# LINK2_LPC4322_PERIPH-DEBUG.net
KiCad netlist of a schematic drawn in Altium Designer
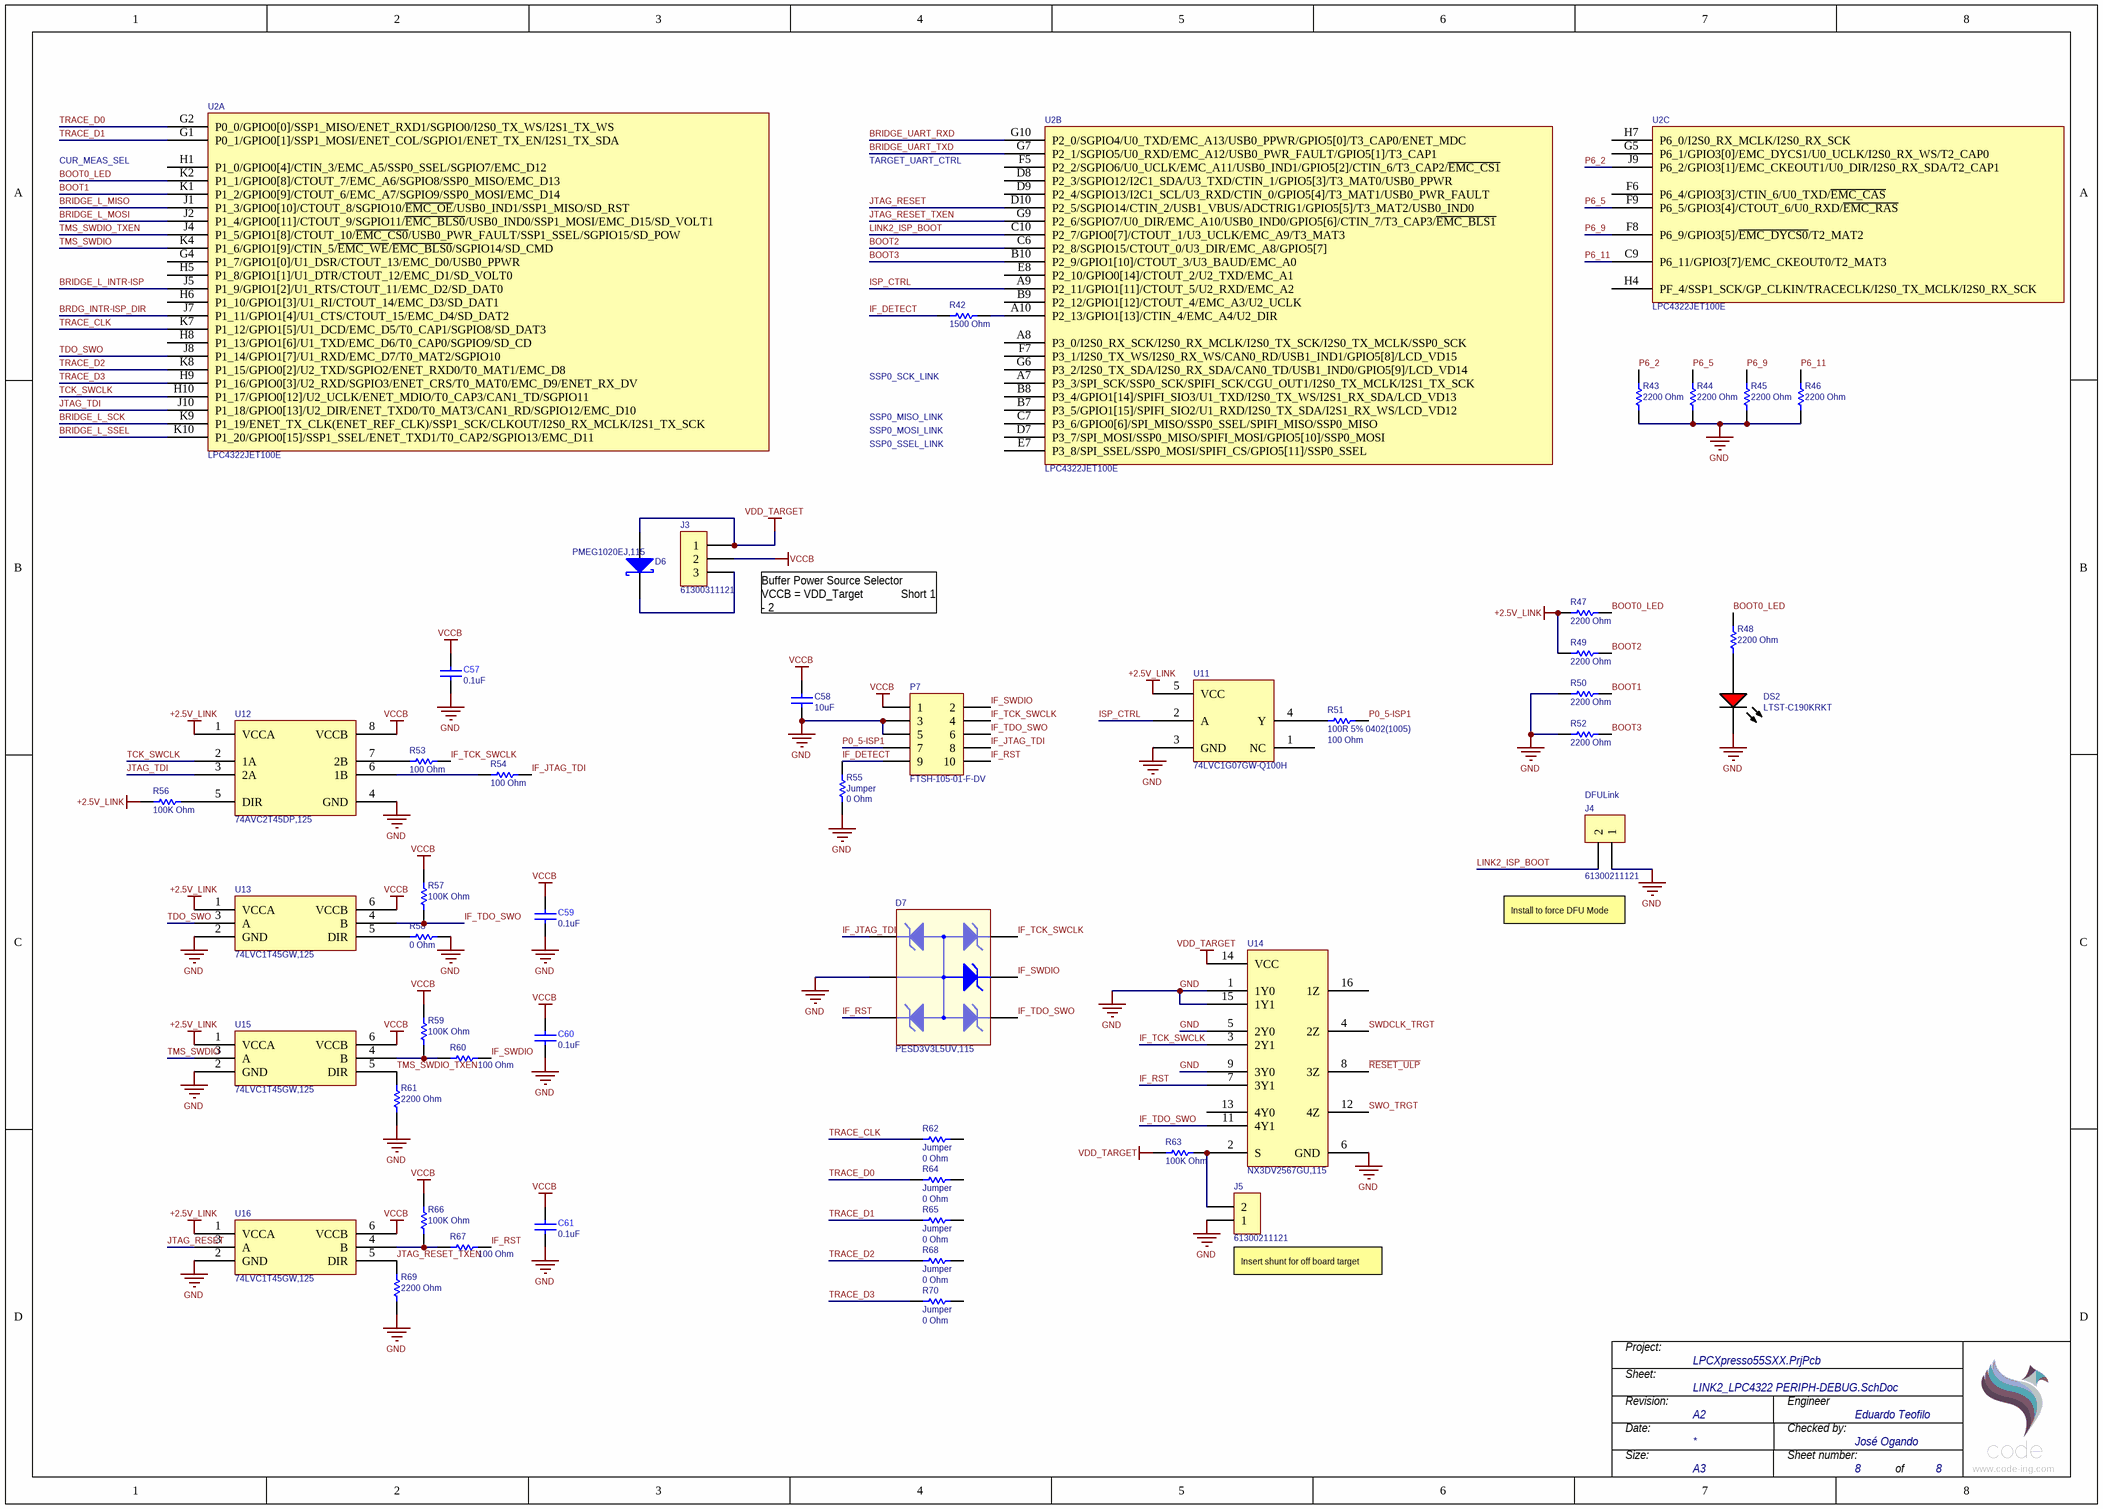
[diagram p0: LINK2_LPC4322 PERIPH-DEBUG.SchDoc]

(export (version "E")
  (design (tool "Eeschema 10.0.6"))
  (components
    (comp (ref "C57")
      (value "0.1uF")
      (footprint "CAPC1005")
      (description "Capacitor, Yageo, Ceramic, 0.1uF 10% 16V 0402 (1005) X7R")
      (fields
        (field (name "TOLERANCE") "10 %")
        (field (name "Comment") "CC0402KRX7R7BB104")
        (field (name "PUBLISHER") "Altium")
      )
      (libsource (lib "Altium Content Vault") (part "CMP-0001-00074-1"))
    )
    (comp (ref "C58")
      (value "10uF")
      (footprint "CAPC0805(2012)145_L")
      (description "CAP 10uF 10V ±10% 0805 (2012 Metric) Thickness 1.45mm SMD")
      (fields (field (name "TOLERANCE") "Â±10%") (field (name "Comment") "CAP 10uF 10V 0805(2012)"))
      (libsource (lib "Altium Content Vault") (part "CMP-1036-04922-1"))
    )
    (comp (ref "C59")
      (value "0.1uF")
      (footprint "CAPC1005")
      (description "Capacitor, Yageo, Ceramic, 0.1uF 10% 16V 0402 (1005) X7R")
      (fields
        (field (name "TOLERANCE") "10 %")
        (field (name "Comment") "CC0402KRX7R7BB104")
        (field (name "PUBLISHER") "Altium")
      )
      (libsource (lib "Altium Content Vault") (part "CMP-0001-00074-1"))
    )
    (comp (ref "C60")
      (value "0.1uF")
      (footprint "CAPC1005")
      (description "Capacitor, Yageo, Ceramic, 0.1uF 10% 16V 0402 (1005) X7R")
      (fields
        (field (name "TOLERANCE") "10 %")
        (field (name "Comment") "CC0402KRX7R7BB104")
        (field (name "PUBLISHER") "Altium")
      )
      (libsource (lib "Altium Content Vault") (part "CMP-0001-00074-1"))
    )
    (comp (ref "C61")
      (value "0.1uF")
      (footprint "CAPC1005")
      (description "Capacitor, Yageo, Ceramic, 0.1uF 10% 16V 0402 (1005) X7R")
      (fields
        (field (name "TOLERANCE") "10 %")
        (field (name "Comment") "CC0402KRX7R7BB104")
        (field (name "PUBLISHER") "Altium")
      )
      (libsource (lib "Altium Content Vault") (part "CMP-0001-00074-1"))
    )
    (comp (ref "D6")
      (value "PMEG1020EJ,115")
      (footprint "SOD-323F, SC90")
      (description "DIODE SCHOTTKY 10V 2A SOD323F")
      (fields
        (field (name "MANUFACTURER") "Nexperia USA Inc.")
        (field (name "CREATED BY") "eteofilo")
        (field (name "MODIFIED BY") "*")
      )
      (libsource (lib "Diodes, Rectifiers - Single") (part "PMEG1020EJ,115"))
    )
    (comp (ref "D7")
      (value "PESD3V3L5UV,115")
      (footprint "SOT-666")
      (description "TVS DIODE 3.3V 12V SOT666")
      (fields
        (field (name "MANUFACTURER") "Nexperia USA Inc.")
        (field (name "MODIFIED BY") "*")
        (field (name "CREATED BY") "eteofilo")
      )
      (libsource (lib "TVS - Diodes") (part "PESD3V3L5UV,115"))
    )
    (comp (ref "DS2")
      (value "LTST-C190KRKT")
      (footprint "LTST-C191KRKT_V")
      (description "LED Uni-Color Red, 62.5 mW, 5 V, -30 to 85 degC, 2-Pin SMD, RoHS, Tape and Reel")
      (fields (field (name "TOLERANCE") "20%"))
      (libsource (lib "Altium Content Vault") (part "LED-RED-AK-2"))
    )
    (comp (ref "J3")
      (value "61300311121")
      (footprint "61300311121")
      (description "HEADER 3POS SNGL T/H 2.54MM")
      (fields
        (field (name "MANUFACTURER") "Wurth Electronics Inc")
        (field (name "MODIFIED BY") "*")
        (field (name "CREATED BY") "gmoreno")
      )
      (libsource (lib "Rectangular - Headers, Male Pins") (part "61300311121"))
    )
    (comp (ref "J4")
      (value "61300211121")
      (footprint "61300211121")
      (description "HEADER 2POS SNGL T/H 2.54MM")
      (fields
        (field (name "MANUFACTURER") "Wurth Electronics Inc")
        (field (name "MODIFIED BY") "*")
        (field (name "CREATED BY") "gmoreno")
      )
      (libsource (lib "") (part "61300211121_1"))
    )
    (comp (ref "J5")
      (value "61300211121")
      (footprint "61300211121")
      (description "HEADER 2POS SNGL T/H 2.54MM")
      (fields
        (field (name "MANUFACTURER") "Wurth Electronics Inc")
        (field (name "MODIFIED BY") "*")
        (field (name "CREATED BY") "gmoreno")
      )
      (libsource (lib "Rectangular - Headers, Male Pins") (part "61300211121"))
    )
    (comp (ref "P7")
      (value "FTSH-105-01-F-DV")
      (footprint "FTSH-105-01-L-DV-K")
      (description "CONN HEADER 10POS DUAL .05\" SMD")
      (fields
        (field (name "MANUFACTURER") "Samtec Inc")
        (field (name "CREATED BY") "gmoreno")
        (field (name "MODIFIED BY") "*")
      )
      (libsource (lib "Rectangular - Headers, Male Pins") (part "FTSH-105-01-F-DV"))
    )
    (comp (ref "R42")
      (value "1500 Ohm")
      (footprint "RESC0402(1005)_L")
      (description "1K5 0.063W 1% 0402 (1005 Metric)  SMD")
      (fields (field (name "TOLERANCE") "1 %") (field (name "POWER") "0.063 W"))
      (libsource (lib "Altium Content Vault") (part "CMP-1011-00528-1"))
    )
    (comp (ref "R43")
      (value "2200 Ohm")
      (footprint "RESC0402(1005)_L")
      (description "2K2 0.063W 1% 0402 (1005 Metric)  SMD")
      (fields (field (name "POWER") "0.063 W") (field (name "TOLERANCE") "1 %"))
      (libsource (lib "Altium Content Vault") (part "CMP-1011-00546-1"))
    )
    (comp (ref "R44")
      (value "2200 Ohm")
      (footprint "RESC0402(1005)_L")
      (description "2K2 0.063W 1% 0402 (1005 Metric)  SMD")
      (fields (field (name "POWER") "0.063 W") (field (name "TOLERANCE") "1 %"))
      (libsource (lib "Altium Content Vault") (part "CMP-1011-00546-1"))
    )
    (comp (ref "R45")
      (value "2200 Ohm")
      (footprint "RESC0402(1005)_L")
      (description "2K2 0.063W 1% 0402 (1005 Metric)  SMD")
      (fields (field (name "POWER") "0.063 W") (field (name "TOLERANCE") "1 %"))
      (libsource (lib "Altium Content Vault") (part "CMP-1011-00546-1"))
    )
    (comp (ref "R46")
      (value "2200 Ohm")
      (footprint "RESC0402(1005)_L")
      (description "2K2 0.063W 1% 0402 (1005 Metric)  SMD")
      (fields (field (name "POWER") "0.063 W") (field (name "TOLERANCE") "1 %"))
      (libsource (lib "Altium Content Vault") (part "CMP-1011-00546-1"))
    )
    (comp (ref "R47")
      (value "2200 Ohm")
      (footprint "RESC0402(1005)_L")
      (description "2K2 0.063W 1% 0402 (1005 Metric)  SMD")
      (fields (field (name "POWER") "0.063 W") (field (name "TOLERANCE") "1 %"))
      (libsource (lib "Altium Content Vault") (part "CMP-1011-00546-1"))
    )
    (comp (ref "R48")
      (value "2200 Ohm")
      (footprint "RESC0402(1005)_L")
      (description "2K2 0.063W 1% 0402 (1005 Metric)  SMD")
      (fields (field (name "POWER") "0.063 W") (field (name "TOLERANCE") "1 %"))
      (libsource (lib "Altium Content Vault") (part "CMP-1011-00546-1"))
    )
    (comp (ref "R49")
      (value "2200 Ohm")
      (footprint "RESC0402(1005)_L")
      (description "2K2 0.063W 1% 0402 (1005 Metric)  SMD")
      (fields (field (name "POWER") "0.063 W") (field (name "TOLERANCE") "1 %"))
      (libsource (lib "Altium Content Vault") (part "CMP-1011-00546-1"))
    )
    (comp (ref "R50")
      (value "2200 Ohm")
      (footprint "RESC0402(1005)_L")
      (description "2K2 0.063W 1% 0402 (1005 Metric)  SMD")
      (fields (field (name "POWER") "0.063 W") (field (name "TOLERANCE") "1 %"))
      (libsource (lib "Altium Content Vault") (part "CMP-1011-00546-1"))
    )
    (comp (ref "R51")
      (value "100R 5% 0402(1005)")
      (footprint "RESC0402(1005)_L")
      (description "100R 0.063W 5% 0402 (1005 Metric)  SMD")
      (fields
        (field (name "POWER") "0.063 W")
        (field (name "ALTIUM_VALUE") "100 Ohm")
        (field (name "TOLERANCE") "5 %")
      )
      (libsource (lib "Altium Content Vault") (part "RES"))
    )
    (comp (ref "R52")
      (value "2200 Ohm")
      (footprint "RESC0402(1005)_L")
      (description "2K2 0.063W 1% 0402 (1005 Metric)  SMD")
      (fields (field (name "POWER") "0.063 W") (field (name "TOLERANCE") "1 %"))
      (libsource (lib "Altium Content Vault") (part "CMP-1011-00546-1"))
    )
    (comp (ref "R53")
      (value "100 Ohm")
      (footprint "RESC0402(1005)_L")
      (description "100R 0.063W 5% 0402 (1005 Metric)  SMD")
      (fields (field (name "POWER") "0.063 W") (field (name "TOLERANCE") "5 %"))
      (libsource (lib "Altium Content Vault") (part "CMP-1011-00050-1"))
    )
    (comp (ref "R54")
      (value "100 Ohm")
      (footprint "RESC0402(1005)_L")
      (description "100R 0.063W 5% 0402 (1005 Metric)  SMD")
      (fields (field (name "POWER") "0.063 W") (field (name "TOLERANCE") "5 %"))
      (libsource (lib "Altium Content Vault") (part "CMP-1011-00050-1"))
    )
    (comp (ref "R55")
      (value "Jumper")
      (footprint "RESC0402(1005)_L")
      (description "Jumper 0402 (1005 Metric)")
      (fields (field (name "TOLERANCE") "None") (field (name "ALTIUM_VALUE") "0 Ohm"))
      (libsource (lib "Altium Content Vault") (part "CMP-1011-00001-1"))
    )
    (comp (ref "R56")
      (value "100K Ohm")
      (footprint "RESC1005X40X25LL05T05")
      (description "Chip Resistor, 100 KOhm, +/- 1%, 100 mW, -55 to 155 degC, 0402 (1005 Metric), RoHS, Tape and Reel")
      (fields (field (name "TOLERANCE") "1%") (field (name "MANUFACTURER") "Basic Passives"))
      (libsource (lib "Altium Content Vault") (part "CMP-2002-00608-3"))
    )
    (comp (ref "R57")
      (value "100K Ohm")
      (footprint "RESC1005X40X25LL05T05")
      (description "Chip Resistor, 100 KOhm, +/- 1%, 100 mW, -55 to 155 degC, 0402 (1005 Metric), RoHS, Tape and Reel")
      (fields (field (name "TOLERANCE") "1%") (field (name "MANUFACTURER") "Basic Passives"))
      (libsource (lib "Altium Content Vault") (part "CMP-2002-00608-3"))
    )
    (comp (ref "R58")
      (value "0 Ohm")
      (footprint "RESC0402(1005)_L")
      (description "Jumper 0402 (1005 Metric)")
      (fields (field (name "TOLERANCE") "None") (field (name "Comment") "Jumper 0402(1005)"))
      (libsource (lib "Altium Content Vault") (part "CMP-1011-00001-1"))
    )
    (comp (ref "R59")
      (value "100K Ohm")
      (footprint "RESC1005X40X25LL05T05")
      (description "Chip Resistor, 100 KOhm, +/- 1%, 100 mW, -55 to 155 degC, 0402 (1005 Metric), RoHS, Tape and Reel")
      (fields (field (name "TOLERANCE") "1%") (field (name "MANUFACTURER") "Basic Passives"))
      (libsource (lib "Altium Content Vault") (part "CMP-2002-00608-3"))
    )
    (comp (ref "R60")
      (value "100 Ohm")
      (footprint "RESC0402(1005)_L")
      (description "100R 0.063W 5% 0402 (1005 Metric)  SMD")
      (fields (field (name "POWER") "0.063 W") (field (name "TOLERANCE") "5 %"))
      (libsource (lib "Altium Content Vault") (part "CMP-1011-00050-1"))
    )
    (comp (ref "R61")
      (value "2200 Ohm")
      (footprint "RESC0402(1005)_L")
      (description "2K2 0.063W 1% 0402 (1005 Metric)  SMD")
      (fields (field (name "POWER") "0.063 W") (field (name "TOLERANCE") "1 %"))
      (libsource (lib "Altium Content Vault") (part "CMP-1011-00546-1"))
    )
    (comp (ref "R62")
      (value "Jumper")
      (footprint "RESC0402(1005)_L")
      (description "Jumper 0402 (1005 Metric)")
      (fields (field (name "TOLERANCE") "None") (field (name "ALTIUM_VALUE") "0 Ohm"))
      (libsource (lib "Altium Content Vault") (part "CMP-1011-00001-1"))
    )
    (comp (ref "R63")
      (value "100K Ohm")
      (footprint "RESC1005X40X25LL05T05")
      (description "Chip Resistor, 100 KOhm, +/- 1%, 100 mW, -55 to 155 degC, 0402 (1005 Metric), RoHS, Tape and Reel")
      (fields (field (name "TOLERANCE") "1%") (field (name "MANUFACTURER") "Basic Passives"))
      (libsource (lib "Altium Content Vault") (part "CMP-2002-00608-3"))
    )
    (comp (ref "R64")
      (value "Jumper")
      (footprint "RESC0402(1005)_L")
      (description "Jumper 0402 (1005 Metric)")
      (fields (field (name "TOLERANCE") "None") (field (name "ALTIUM_VALUE") "0 Ohm"))
      (libsource (lib "Altium Content Vault") (part "CMP-1011-00001-1"))
    )
    (comp (ref "R65")
      (value "Jumper")
      (footprint "RESC0402(1005)_L")
      (description "Jumper 0402 (1005 Metric)")
      (fields (field (name "TOLERANCE") "None") (field (name "ALTIUM_VALUE") "0 Ohm"))
      (libsource (lib "Altium Content Vault") (part "CMP-1011-00001-1"))
    )
    (comp (ref "R66")
      (value "100K Ohm")
      (footprint "RESC1005X40X25LL05T05")
      (description "Chip Resistor, 100 KOhm, +/- 1%, 100 mW, -55 to 155 degC, 0402 (1005 Metric), RoHS, Tape and Reel")
      (fields (field (name "TOLERANCE") "1%") (field (name "MANUFACTURER") "Basic Passives"))
      (libsource (lib "Altium Content Vault") (part "CMP-2002-00608-3"))
    )
    (comp (ref "R67")
      (value "100 Ohm")
      (footprint "RESC0402(1005)_L")
      (description "100R 0.063W 5% 0402 (1005 Metric)  SMD")
      (fields (field (name "POWER") "0.063 W") (field (name "TOLERANCE") "5 %"))
      (libsource (lib "Altium Content Vault") (part "CMP-1011-00050-1"))
    )
    (comp (ref "R68")
      (value "Jumper")
      (footprint "RESC0402(1005)_L")
      (description "Jumper 0402 (1005 Metric)")
      (fields (field (name "TOLERANCE") "None") (field (name "ALTIUM_VALUE") "0 Ohm"))
      (libsource (lib "Altium Content Vault") (part "CMP-1011-00001-1"))
    )
    (comp (ref "R69")
      (value "2200 Ohm")
      (footprint "RESC0402(1005)_L")
      (description "2K2 0.063W 1% 0402 (1005 Metric)  SMD")
      (fields (field (name "POWER") "0.063 W") (field (name "TOLERANCE") "1 %"))
      (libsource (lib "Altium Content Vault") (part "CMP-1011-00546-1"))
    )
    (comp (ref "R70")
      (value "Jumper")
      (footprint "RESC0402(1005)_L")
      (description "Jumper 0402 (1005 Metric)")
      (fields (field (name "TOLERANCE") "None") (field (name "ALTIUM_VALUE") "0 Ohm"))
      (libsource (lib "Altium Content Vault") (part "CMP-1011-00001-1"))
    )
    (comp (ref "U2")
      (value "LPC4322JET100E")
      (footprint "BGA100_9x9x1.2mm")
      (description "IC MCU 32BIT 512KB FLASH 100BGA")
      (fields
        (field (name "MANUFACTURER") "NXP")
        (field (name "CREATED BY") "eteofilo")
        (field (name "MODIFIED BY") "*")
      )
      (libsource (lib "Embedded - Microcontrollers") (part "LPC4322JET100E"))
    )
    (comp (ref "U11")
      (value "74LVC1G07GW-Q100H")
      (footprint "SOT353")
      (description "IC BUFF OPEN DRAIN N-INV 5TSSOP")
      (fields
        (field (name "MANUFACTURER") "Nexperia USA Inc.")
        (field (name "MODIFIED BY") "*")
        (field (name "CREATED BY") "eteofilo")
      )
      (libsource (lib "Logic - Buffers, Drivers, Receivers, Transceivers") (part "74LVC1G07GW-Q100H"))
    )
    (comp (ref "U12")
      (value "74AVC2T45DP,125")
      (footprint "TSSOP8")
      (description "IC BUS TRANSCVR TRI-ST DL 8TSSOP")
      (fields
        (field (name "MANUFACTURER") "Nexperia USA Inc.")
        (field (name "CREATED BY") "eteofilo")
        (field (name "MODIFIED BY") "*")
      )
      (libsource (lib "Logic - Translators") (part "74AVC2T45DP,125"))
    )
    (comp (ref "U13")
      (value "74LVC1T45GW,125")
      (footprint "SOT-363")
      (description "TXRX XLATING DUAL 3ST 6TSSOP")
      (fields
        (field (name "MANUFACTURER") "Nexperia USA Inc.")
        (field (name "CREATED BY") "eteofilo")
        (field (name "MODIFIED BY") "*")
      )
      (libsource (lib "Logic - Translators") (part "74LVC1T45GW,125"))
    )
    (comp (ref "U14")
      (value "NX3DV2567GU,115")
      (footprint "XQFN16")
      (description "IC ANLG SWITCH 4PDT 16XQFN")
      (fields
        (field (name "MANUFACTURER") "NXP USA Inc.")
        (field (name "MODIFIED BY") "*")
        (field (name "CREATED BY") "eteofilo")
      )
      (libsource (lib "Interface - Analog Switches") (part "NX3DV2567GU,115"))
    )
    (comp (ref "U15")
      (value "74LVC1T45GW,125")
      (footprint "SOT-363")
      (description "TXRX XLATING DUAL 3ST 6TSSOP")
      (fields
        (field (name "MANUFACTURER") "Nexperia USA Inc.")
        (field (name "CREATED BY") "eteofilo")
        (field (name "MODIFIED BY") "*")
      )
      (libsource (lib "Logic - Translators") (part "74LVC1T45GW,125"))
    )
    (comp (ref "U16")
      (value "74LVC1T45GW,125")
      (footprint "SOT-363")
      (description "TXRX XLATING DUAL 3ST 6TSSOP")
      (fields
        (field (name "MANUFACTURER") "Nexperia USA Inc.")
        (field (name "CREATED BY") "eteofilo")
        (field (name "MODIFIED BY") "*")
      )
      (libsource (lib "Logic - Translators") (part "74LVC1T45GW,125"))
    )
  )
  (nets
    (net (code "1") (name "+2.5V_LINK") (class "Default")
      (node (ref "R47") (pin "2") (pinfunction "2_2") (pintype "passive"))
      (node (ref "R49") (pin "2") (pinfunction "2_2") (pintype "passive"))
      (node (ref "R56") (pin "1") (pinfunction "1_1") (pintype "passive"))
      (node (ref "U11") (pin "5") (pinfunction "VCC_5") (pintype "passive"))
      (node (ref "U12") (pin "1") (pinfunction "VCCA_1") (pintype "passive"))
      (node (ref "U13") (pin "1") (pinfunction "VCCA_1") (pintype "passive"))
      (node (ref "U15") (pin "1") (pinfunction "VCCA_1") (pintype "passive"))
      (node (ref "U16") (pin "1") (pinfunction "VCCA_1") (pintype "passive"))
    )
    (net (code "2") (name "/BOOT0_LED") (class "Default")
      (node (ref "R47") (pin "1") (pinfunction "1_1") (pintype "passive"))
      (node (ref "R48") (pin "2") (pinfunction "2_2") (pintype "passive"))
      (node (ref "U2") (pin "K2") (pinfunction "P1_1/GPIO0[8]/CTOUT_7/EMC_A6/SGPIO8/SSP0_MISO/EMC_D13_K2") (pintype "passive"))
    )
    (net (code "3") (name "/BOOT1") (class "Default")
      (node (ref "R50") (pin "1") (pinfunction "1_1") (pintype "passive"))
      (node (ref "U2") (pin "K1") (pinfunction "P1_2/GPIO0[9]/CTOUT_6/EMC_A7/SGPIO9/SSP0_MOSI/EMC_D14_K1") (pintype "passive"))
    )
    (net (code "4") (name "/BOOT2") (class "Default")
      (node (ref "R49") (pin "1") (pinfunction "1_1") (pintype "passive"))
      (node (ref "U2") (pin "C6") (pinfunction "P2_8/SGPIO15/CTOUT_0/U3_DIR/EMC_A8/GPIO5[7]_C6") (pintype "passive"))
    )
    (net (code "5") (name "/BOOT3") (class "Default")
      (node (ref "R52") (pin "1") (pinfunction "1_1") (pintype "passive"))
      (node (ref "U2") (pin "B10") (pinfunction "P2_9/GPIO1[10]/CTOUT_3/U3_BAUD/EMC_A0_B10") (pintype "passive"))
    )
    (net (code "6") (name "/BRDG_INTR-ISP_DIR") (class "Default")
      (node (ref "U2") (pin "J7") (pinfunction "P1_11/GPIO1[4]/U1_CTS/CTOUT_15/EMC_D4/SD_DAT2_J7") (pintype "passive"))
    )
    (net (code "7") (name "/BRIDGE_L_INTR-ISP") (class "Default")
      (node (ref "U2") (pin "J5") (pinfunction "P1_9/GPIO1[2]/U1_RTS/CTOUT_11/EMC_D2/SD_DAT0_J5") (pintype "passive"))
    )
    (net (code "8") (name "/BRIDGE_L_MISO") (class "Default")
      (node (ref "U2") (pin "J1") (pinfunction "P1_3/GPIO0[10]/CTOUT_8/SGPIO10/~{EMC_OE}/USB0_IND1/SSP1_MISO/SD_RST_J1") (pintype "passive"))
    )
    (net (code "9") (name "/BRIDGE_L_MOSI") (class "Default")
      (node (ref "U2") (pin "J2") (pinfunction "P1_4/GPIO0[11]/CTOUT_9/SGPIO11/~{EMC_BLS0}/USB0_IND0/SSP1_MOSI/EMC_D15/SD_VOLT1_J2") (pintype "passive"))
    )
    (net (code "10") (name "/BRIDGE_L_SCK") (class "Default")
      (node (ref "U2") (pin "K9") (pinfunction "P1_19/ENET_TX_CLK(ENET_REF_CLK)/SSP1_SCK/CLKOUT/I2S0_RX_MCLK/I2S1_TX_SCK_K9") (pintype "passive"))
    )
    (net (code "11") (name "/BRIDGE_L_SSEL") (class "Default")
      (node (ref "U2") (pin "K10") (pinfunction "P1_20/GPIO0[15]/SSP1_SSEL/ENET_TXD1/T0_CAP2/SGPIO13/EMC_D11_K10") (pintype "passive"))
    )
    (net (code "12") (name "/BRIDGE_UART_RXD") (class "Default")
      (node (ref "U2") (pin "G10") (pinfunction "P2_0/SGPIO4/U0_TXD/EMC_A13/USB0_PPWR/GPIO5[0]/T3_CAP0/ENET_MDC_G10") (pintype "passive"))
    )
    (net (code "13") (name "/BRIDGE_UART_TXD") (class "Default")
      (node (ref "U2") (pin "G7") (pinfunction "P2_1/SGPIO5/U0_RXD/EMC_A12/USB0_PWR_FAULT/GPIO5[1]/T3_CAP1_G7") (pintype "passive"))
    )
    (net (code "14") (name "/IF_DETECT") (class "Default")
      (node (ref "P7") (pin "9") (pinfunction "9_9") (pintype "passive"))
      (node (ref "R42") (pin "1") (pinfunction "1_1") (pintype "passive"))
      (node (ref "R55") (pin "2") (pinfunction "2_2") (pintype "passive"))
    )
    (net (code "15") (name "/IF_JTAG_TDI") (class "Default")
      (node (ref "D7") (pin "1") (pinfunction "I/O1_1") (pintype "passive"))
      (node (ref "P7") (pin "8") (pinfunction "8_8") (pintype "passive"))
      (node (ref "R54") (pin "2") (pinfunction "2_2") (pintype "passive"))
    )
    (net (code "16") (name "/IF_RST") (class "Default")
      (node (ref "D7") (pin "3") (pinfunction "I/O2_3") (pintype "passive"))
      (node (ref "P7") (pin "10") (pinfunction "10_10") (pintype "passive"))
      (node (ref "R67") (pin "2") (pinfunction "2_2") (pintype "passive"))
      (node (ref "U14") (pin "7") (pinfunction "3Y1_7") (pintype "passive"))
    )
    (net (code "17") (name "/IF_SWDIO") (class "Default")
      (node (ref "D7") (pin "5") (pinfunction "I/O4_5") (pintype "passive"))
      (node (ref "P7") (pin "2") (pinfunction "2_2") (pintype "passive"))
      (node (ref "R60") (pin "2") (pinfunction "2_2") (pintype "passive"))
    )
    (net (code "18") (name "/IF_TCK_SWCLK") (class "Default")
      (node (ref "D7") (pin "6") (pinfunction "I/O5_6") (pintype "passive"))
      (node (ref "P7") (pin "4") (pinfunction "4_4") (pintype "passive"))
      (node (ref "R53") (pin "2") (pinfunction "2_2") (pintype "passive"))
      (node (ref "U14") (pin "3") (pinfunction "2Y1_3") (pintype "passive"))
    )
    (net (code "19") (name "/IF_TDO_SWO") (class "Default")
      (node (ref "D7") (pin "4") (pinfunction "I/O3_4") (pintype "passive"))
      (node (ref "P7") (pin "6") (pinfunction "6_6") (pintype "passive"))
      (node (ref "R57") (pin "1") (pinfunction "1_1") (pintype "passive"))
      (node (ref "U13") (pin "4") (pinfunction "B_4") (pintype "passive"))
      (node (ref "U14") (pin "11") (pinfunction "4Y1_11") (pintype "passive"))
    )
    (net (code "20") (name "/ISP_CTRL") (class "Default")
      (node (ref "U11") (pin "2") (pinfunction "A_2") (pintype "passive"))
      (node (ref "U2") (pin "A9") (pinfunction "P2_11/GPIO1[11]/CTOUT_5/U2_RXD/EMC_A2_A9") (pintype "passive"))
    )
    (net (code "21") (name "/JTAG_RESET") (class "Default")
      (node (ref "U16") (pin "3") (pinfunction "A_3") (pintype "passive"))
      (node (ref "U2") (pin "D10") (pinfunction "P2_5/SGPIO14/CTIN_2/USB1_VBUS/ADCTRIG1/GPIO5[5]/T3_MAT2/USB0_IND0_D10") (pintype "passive"))
    )
    (net (code "22") (name "/JTAG_RESET_TXEN") (class "Default")
      (node (ref "R69") (pin "2") (pinfunction "2_2") (pintype "passive"))
      (node (ref "U16") (pin "5") (pinfunction "DIR_5") (pintype "passive"))
      (node (ref "U2") (pin "G9") (pinfunction "P2_6/SGPIO7/U0_DIR/EMC_A10/USB0_IND0/GPIO5[6]/CTIN_7/T3_CAP3/~{EMC_BLS1}_G9") (pintype "passive"))
    )
    (net (code "23") (name "/JTAG_TDI") (class "Default")
      (node (ref "U12") (pin "3") (pinfunction "2A_3") (pintype "passive"))
      (node (ref "U2") (pin "J10") (pinfunction "P1_18/GPIO0[13]/U2_DIR/ENET_TXD0/T0_MAT3/CAN1_RD/SGPIO12/EMC_D10_J10") (pintype "passive"))
    )
    (net (code "24") (name "/LINK2_ISP_BOOT") (class "Default")
      (node (ref "J4") (pin "2") (pinfunction "2_2") (pintype "passive"))
      (node (ref "U2") (pin "C10") (pinfunction "P2_7/GPIO0[7]/CTOUT_1/U3_UCLK/EMC_A9/T3_MAT3_C10") (pintype "passive"))
    )
    (net (code "25") (name "/P0_5-ISP1") (class "Default")
      (node (ref "P7") (pin "7") (pinfunction "7_7") (pintype "passive"))
      (node (ref "R51") (pin "2") (pinfunction "2_2") (pintype "passive"))
    )
    (net (code "26") (name "/P6_2") (class "Default")
      (node (ref "R43") (pin "2") (pinfunction "2_2") (pintype "passive"))
      (node (ref "U2") (pin "J9") (pinfunction "P6_2/GPIO3[1]/EMC_CKEOUT1/U0_DIR/I2S0_RX_SDA/T2_CAP1_J9") (pintype "passive"))
    )
    (net (code "27") (name "/P6_5") (class "Default")
      (node (ref "R44") (pin "2") (pinfunction "2_2") (pintype "passive"))
      (node (ref "U2") (pin "F9") (pinfunction "P6_5/GPIO3[4]/CTOUT_6/U0_RXD/~{EMC_RAS}_F9") (pintype "passive"))
    )
    (net (code "28") (name "/P6_9") (class "Default")
      (node (ref "R45") (pin "2") (pinfunction "2_2") (pintype "passive"))
      (node (ref "U2") (pin "F8") (pinfunction "P6_9/GPIO3[5]/~{EMC_DYCS0}/T2_MAT2_F8") (pintype "passive"))
    )
    (net (code "29") (name "/P6_11") (class "Default")
      (node (ref "R46") (pin "2") (pinfunction "2_2") (pintype "passive"))
      (node (ref "U2") (pin "C9") (pinfunction "P6_11/GPIO3[7]/EMC_CKEOUT0/T2_MAT3_C9") (pintype "passive"))
    )
    (net (code "30") (name "/SWDCLK_TRGT") (class "Default")
      (node (ref "U14") (pin "4") (pinfunction "2Z_4") (pintype "passive"))
    )
    (net (code "31") (name "/SWO_TRGT") (class "Default")
      (node (ref "U14") (pin "12") (pinfunction "4Z_12") (pintype "passive"))
    )
    (net (code "32") (name "/TCK_SWCLK") (class "Default")
      (node (ref "U12") (pin "2") (pinfunction "1A_2") (pintype "passive"))
      (node (ref "U2") (pin "H10") (pinfunction "P1_17/GPIO0[12]/U2_UCLK/ENET_MDIO/T0_CAP3/CAN1_TD/SGPIO11_H10") (pintype "passive"))
    )
    (net (code "33") (name "/TDO_SWO") (class "Default")
      (node (ref "U13") (pin "3") (pinfunction "A_3") (pintype "passive"))
      (node (ref "U2") (pin "J8") (pinfunction "P1_14/GPIO1[7]/U1_RXD/EMC_D7/T0_MAT2/SGPIO10_J8") (pintype "passive"))
    )
    (net (code "34") (name "/TMS_SWDIO") (class "Default")
      (node (ref "U15") (pin "3") (pinfunction "A_3") (pintype "passive"))
      (node (ref "U2") (pin "K4") (pinfunction "P1_6/GPIO1[9]/CTIN_5/~{EMC_WE}/~{EMC_BLS0}/SGPIO14/SD_CMD_K4") (pintype "passive"))
    )
    (net (code "35") (name "/TMS_SWDIO_TXEN") (class "Default")
      (node (ref "R61") (pin "2") (pinfunction "2_2") (pintype "passive"))
      (node (ref "U15") (pin "5") (pinfunction "DIR_5") (pintype "passive"))
      (node (ref "U2") (pin "J4") (pinfunction "P1_5/GPIO1[8]/CTOUT_10/~{EMC_CS0}/USB0_PWR_FAULT/SSP1_SSEL/SGPIO15/SD_POW_J4") (pintype "passive"))
    )
    (net (code "36") (name "/TRACE_CLK") (class "Default")
      (node (ref "R62") (pin "1") (pinfunction "1_1") (pintype "passive"))
      (node (ref "U2") (pin "K7") (pinfunction "P1_12/GPIO1[5]/U1_DCD/EMC_D5/T0_CAP1/SGPIO8/SD_DAT3_K7") (pintype "passive"))
    )
    (net (code "37") (name "/TRACE_D0") (class "Default")
      (node (ref "R64") (pin "1") (pinfunction "1_1") (pintype "passive"))
      (node (ref "U2") (pin "G2") (pinfunction "P0_0/GPIO0[0]/SSP1_MISO/ENET_RXD1/SGPIO0/I2S0_TX_WS/I2S1_TX_WS_G2") (pintype "passive"))
    )
    (net (code "38") (name "/TRACE_D1") (class "Default")
      (node (ref "R65") (pin "1") (pinfunction "1_1") (pintype "passive"))
      (node (ref "U2") (pin "G1") (pinfunction "P0_1/GPIO0[1]/SSP1_MOSI/ENET_COL/SGPIO1/ENET_TX_EN/I2S1_TX_SDA_G1") (pintype "passive"))
    )
    (net (code "39") (name "/TRACE_D2") (class "Default")
      (node (ref "R68") (pin "1") (pinfunction "1_1") (pintype "passive"))
      (node (ref "U2") (pin "K8") (pinfunction "P1_15/GPIO0[2]/U2_TXD/SGPIO2/ENET_RXD0/T0_MAT1/EMC_D8_K8") (pintype "passive"))
    )
    (net (code "40") (name "/TRACE_D3") (class "Default")
      (node (ref "R70") (pin "1") (pinfunction "1_1") (pintype "passive"))
      (node (ref "U2") (pin "H9") (pinfunction "P1_16/GPIO0[3]/U2_RXD/SGPIO3/ENET_CRS/T0_MAT0/EMC_D9/ENET_RX_DV_H9") (pintype "passive"))
    )
    (net (code "41") (name "/~{RESET_ULP}") (class "Default")
      (node (ref "U14") (pin "8") (pinfunction "3Z_8") (pintype "passive"))
    )
    (net (code "42") (name "GND") (class "Default")
      (node (ref "C57") (pin "2") (pinfunction "2_2") (pintype "passive"))
      (node (ref "C58") (pin "1") (pinfunction "1_1") (pintype "passive"))
      (node (ref "C59") (pin "2") (pinfunction "2_2") (pintype "passive"))
      (node (ref "C60") (pin "2") (pinfunction "2_2") (pintype "passive"))
      (node (ref "C61") (pin "2") (pinfunction "2_2") (pintype "passive"))
      (node (ref "D7") (pin "2") (pinfunction "GND_2") (pintype "passive"))
      (node (ref "DS2") (pin "2") (pinfunction "K_2") (pintype "passive"))
      (node (ref "J4") (pin "1") (pinfunction "1_1") (pintype "passive"))
      (node (ref "J5") (pin "1") (pinfunction "1_1") (pintype "passive"))
      (node (ref "P7") (pin "3") (pinfunction "3_3") (pintype "passive"))
      (node (ref "P7") (pin "5") (pinfunction "5_5") (pintype "passive"))
      (node (ref "R43") (pin "1") (pinfunction "1_1") (pintype "passive"))
      (node (ref "R44") (pin "1") (pinfunction "1_1") (pintype "passive"))
      (node (ref "R45") (pin "1") (pinfunction "1_1") (pintype "passive"))
      (node (ref "R46") (pin "1") (pinfunction "1_1") (pintype "passive"))
      (node (ref "R50") (pin "2") (pinfunction "2_2") (pintype "passive"))
      (node (ref "R52") (pin "2") (pinfunction "2_2") (pintype "passive"))
      (node (ref "R55") (pin "1") (pinfunction "1_1") (pintype "passive"))
      (node (ref "R58") (pin "1") (pinfunction "1_1") (pintype "passive"))
      (node (ref "R61") (pin "1") (pinfunction "1_1") (pintype "passive"))
      (node (ref "R69") (pin "1") (pinfunction "1_1") (pintype "passive"))
      (node (ref "U11") (pin "3") (pinfunction "GND_3") (pintype "passive"))
      (node (ref "U12") (pin "4") (pinfunction "GND_4") (pintype "passive"))
      (node (ref "U13") (pin "2") (pinfunction "GND_2") (pintype "passive"))
      (node (ref "U14") (pin "1") (pinfunction "1Y0_1") (pintype "passive"))
      (node (ref "U14") (pin "15") (pinfunction "1Y1_15") (pintype "passive"))
      (node (ref "U14") (pin "5") (pinfunction "2Y0_5") (pintype "passive"))
      (node (ref "U14") (pin "6") (pinfunction "GND_6") (pintype "passive"))
      (node (ref "U14") (pin "9") (pinfunction "3Y0_9") (pintype "passive"))
      (node (ref "U15") (pin "2") (pinfunction "GND_2") (pintype "passive"))
      (node (ref "U16") (pin "2") (pinfunction "GND_2") (pintype "passive"))
    )
    (net (code "43") (name "Net-(D6-K)") (class "Default")
      (node (ref "D6") (pin "1") (pinfunction "K_1") (pintype "passive"))
      (node (ref "J3") (pin "3") (pinfunction "3_3") (pintype "passive"))
    )
    (net (code "44") (name "Net-(DS2-A)") (class "Default")
      (node (ref "DS2") (pin "1") (pinfunction "A_1") (pintype "passive"))
      (node (ref "R48") (pin "1") (pinfunction "1_1") (pintype "passive"))
    )
    (net (code "45") (name "Net-(U2B-P2_13{slash}GPIO1[13]{slash}CTIN_4{slash}EMC_A4{slash}U2_DIR)") (class "Default")
      (node (ref "R42") (pin "2") (pinfunction "2_2") (pintype "passive"))
      (node (ref "U2") (pin "A10") (pinfunction "P2_13/GPIO1[13]/CTIN_4/EMC_A4/U2_DIR_A10") (pintype "passive"))
    )
    (net (code "46") (name "Net-(U11-Y)") (class "Default")
      (node (ref "R51") (pin "1") (pinfunction "1_1") (pintype "passive"))
      (node (ref "U11") (pin "4") (pinfunction "Y_4") (pintype "passive"))
    )
    (net (code "47") (name "Net-(U12-1B)") (class "Default")
      (node (ref "R54") (pin "1") (pinfunction "1_1") (pintype "passive"))
      (node (ref "U12") (pin "6") (pinfunction "1B_6") (pintype "passive"))
    )
    (net (code "48") (name "Net-(U12-2B)") (class "Default")
      (node (ref "R53") (pin "1") (pinfunction "1_1") (pintype "passive"))
      (node (ref "U12") (pin "7") (pinfunction "2B_7") (pintype "passive"))
    )
    (net (code "49") (name "Net-(U12-DIR)") (class "Default")
      (node (ref "R56") (pin "2") (pinfunction "2_2") (pintype "passive"))
      (node (ref "U12") (pin "5") (pinfunction "DIR_5") (pintype "passive"))
    )
    (net (code "50") (name "Net-(U13-DIR)") (class "Default")
      (node (ref "R58") (pin "2") (pinfunction "2_2") (pintype "passive"))
      (node (ref "U13") (pin "5") (pinfunction "DIR_5") (pintype "passive"))
    )
    (net (code "51") (name "Net-(U14-S)") (class "Default")
      (node (ref "J5") (pin "2") (pinfunction "2_2") (pintype "passive"))
      (node (ref "R63") (pin "1") (pinfunction "1_1") (pintype "passive"))
      (node (ref "U14") (pin "2") (pinfunction "S_2") (pintype "passive"))
    )
    (net (code "52") (name "Net-(U15-B)") (class "Default")
      (node (ref "R59") (pin "1") (pinfunction "1_1") (pintype "passive"))
      (node (ref "R60") (pin "1") (pinfunction "1_1") (pintype "passive"))
      (node (ref "U15") (pin "4") (pinfunction "B_4") (pintype "passive"))
    )
    (net (code "53") (name "Net-(U16-B)") (class "Default")
      (node (ref "R66") (pin "1") (pinfunction "1_1") (pintype "passive"))
      (node (ref "R67") (pin "1") (pinfunction "1_1") (pintype "passive"))
      (node (ref "U16") (pin "4") (pinfunction "B_4") (pintype "passive"))
    )
    (net (code "54") (name "VCCB") (class "Default")
      (node (ref "C57") (pin "1") (pinfunction "1_1") (pintype "passive"))
      (node (ref "C58") (pin "2") (pinfunction "2_2") (pintype "passive"))
      (node (ref "C59") (pin "1") (pinfunction "1_1") (pintype "passive"))
      (node (ref "C60") (pin "1") (pinfunction "1_1") (pintype "passive"))
      (node (ref "C61") (pin "1") (pinfunction "1_1") (pintype "passive"))
      (node (ref "J3") (pin "2") (pinfunction "2_2") (pintype "passive"))
      (node (ref "P7") (pin "1") (pinfunction "1_1") (pintype "passive"))
      (node (ref "R57") (pin "2") (pinfunction "2_2") (pintype "passive"))
      (node (ref "R59") (pin "2") (pinfunction "2_2") (pintype "passive"))
      (node (ref "R66") (pin "2") (pinfunction "2_2") (pintype "passive"))
      (node (ref "U12") (pin "8") (pinfunction "VCCB_8") (pintype "passive"))
      (node (ref "U13") (pin "6") (pinfunction "VCCB_6") (pintype "passive"))
      (node (ref "U15") (pin "6") (pinfunction "VCCB_6") (pintype "passive"))
      (node (ref "U16") (pin "6") (pinfunction "VCCB_6") (pintype "passive"))
    )
    (net (code "55") (name "VDD_TARGET") (class "Default")
      (node (ref "D6") (pin "2") (pinfunction "A_2") (pintype "passive"))
      (node (ref "J3") (pin "1") (pinfunction "1_1") (pintype "passive"))
      (node (ref "R63") (pin "2") (pinfunction "2_2") (pintype "passive"))
      (node (ref "U14") (pin "14") (pinfunction "VCC_14") (pintype "passive"))
    )
    (net (code "56") (name "unconnected-(R62-Pad2)") (class "Default")
      (node (ref "R62") (pin "2") (pinfunction "2_2") (pintype "passive"))
    )
    (net (code "57") (name "unconnected-(R64-Pad2)") (class "Default")
      (node (ref "R64") (pin "2") (pinfunction "2_2") (pintype "passive"))
    )
    (net (code "58") (name "unconnected-(R65-Pad2)") (class "Default")
      (node (ref "R65") (pin "2") (pinfunction "2_2") (pintype "passive"))
    )
    (net (code "59") (name "unconnected-(R68-Pad2)") (class "Default")
      (node (ref "R68") (pin "2") (pinfunction "2_2") (pintype "passive"))
    )
    (net (code "60") (name "unconnected-(R70-Pad2)") (class "Default")
      (node (ref "R70") (pin "2") (pinfunction "2_2") (pintype "passive"))
    )
    (net (code "61") (name "unconnected-(U2A-P1_0{slash}GPIO0[4]{slash}CTIN_3{slash}EMC_A5{slash}SSP0_SSEL{slash}SGPIO7{slash}EMC_D12-PadH1)") (class "Default")
      (node (ref "U2") (pin "H1") (pinfunction "P1_0/GPIO0[4]/CTIN_3/EMC_A5/SSP0_SSEL/SGPIO7/EMC_D12_H1") (pintype "passive"))
    )
    (net (code "62") (name "unconnected-(U2A-P1_7{slash}GPIO1[0]{slash}U1_DSR{slash}CTOUT_13{slash}EMC_D0{slash}USB0_PPWR-PadG4)") (class "Default")
      (node (ref "U2") (pin "G4") (pinfunction "P1_7/GPIO1[0]/U1_DSR/CTOUT_13/EMC_D0/USB0_PPWR_G4") (pintype "passive"))
    )
    (net (code "63") (name "unconnected-(U2A-P1_8{slash}GPIO1[1]{slash}U1_DTR{slash}CTOUT_12{slash}EMC_D1{slash}SD_VOLT0-PadH5)") (class "Default")
      (node (ref "U2") (pin "H5") (pinfunction "P1_8/GPIO1[1]/U1_DTR/CTOUT_12/EMC_D1/SD_VOLT0_H5") (pintype "passive"))
    )
    (net (code "64") (name "unconnected-(U2A-P1_10{slash}GPIO1[3]{slash}U1_RI{slash}CTOUT_14{slash}EMC_D3{slash}SD_DAT1-PadH6)") (class "Default")
      (node (ref "U2") (pin "H6") (pinfunction "P1_10/GPIO1[3]/U1_RI/CTOUT_14/EMC_D3/SD_DAT1_H6") (pintype "passive"))
    )
    (net (code "65") (name "unconnected-(U2A-P1_13{slash}GPIO1[6]{slash}U1_TXD{slash}EMC_D6{slash}T0_CAP0{slash}SGPIO9{slash}SD_CD-PadH8)") (class "Default")
      (node (ref "U2") (pin "H8") (pinfunction "P1_13/GPIO1[6]/U1_TXD/EMC_D6/T0_CAP0/SGPIO9/SD_CD_H8") (pintype "passive"))
    )
    (net (code "66") (name "unconnected-(U2B-P2_2{slash}SGPIO6{slash}U0_UCLK{slash}EMC_A11{slash}USB0_IND1{slash}GPIO5[2]{slash}CTIN_6{slash}T3_CAP2{slash}~{EMC_CS1}-PadF5)") (class "Default")
      (node (ref "U2") (pin "F5") (pinfunction "P2_2/SGPIO6/U0_UCLK/EMC_A11/USB0_IND1/GPIO5[2]/CTIN_6/T3_CAP2/~{EMC_CS1}_F5") (pintype "passive"))
    )
    (net (code "67") (name "unconnected-(U2B-P2_3{slash}SGPIO12{slash}I2C1_SDA{slash}U3_TXD{slash}CTIN_1{slash}GPIO5[3]{slash}T3_MAT0{slash}USB0_PPWR-PadD8)") (class "Default")
      (node (ref "U2") (pin "D8") (pinfunction "P2_3/SGPIO12/I2C1_SDA/U3_TXD/CTIN_1/GPIO5[3]/T3_MAT0/USB0_PPWR_D8") (pintype "passive"))
    )
    (net (code "68") (name "unconnected-(U2B-P2_4{slash}SGPIO13{slash}I2C1_SCL{slash}U3_RXD{slash}CTIN_0{slash}GPIO5[4]{slash}T3_MAT1{slash}USB0_PWR_FAULT-PadD9)") (class "Default")
      (node (ref "U2") (pin "D9") (pinfunction "P2_4/SGPIO13/I2C1_SCL/U3_RXD/CTIN_0/GPIO5[4]/T3_MAT1/USB0_PWR_FAULT_D9") (pintype "passive"))
    )
    (net (code "69") (name "unconnected-(U2B-P2_10{slash}GPIO0[14]{slash}CTOUT_2{slash}U2_TXD{slash}EMC_A1-PadE8)") (class "Default")
      (node (ref "U2") (pin "E8") (pinfunction "P2_10/GPIO0[14]/CTOUT_2/U2_TXD/EMC_A1_E8") (pintype "passive"))
    )
    (net (code "70") (name "unconnected-(U2B-P2_12{slash}GPIO1[12]{slash}CTOUT_4{slash}EMC_A3{slash}U2_UCLK-PadB9)") (class "Default")
      (node (ref "U2") (pin "B9") (pinfunction "P2_12/GPIO1[12]/CTOUT_4/EMC_A3/U2_UCLK_B9") (pintype "passive"))
    )
    (net (code "71") (name "unconnected-(U2B-P3_0{slash}I2S0_RX_SCK{slash}I2S0_RX_MCLK{slash}I2S0_TX_SCK{slash}I2S0_TX_MCLK{slash}SSP0_SCK-PadA8)") (class "Default")
      (node (ref "U2") (pin "A8") (pinfunction "P3_0/I2S0_RX_SCK/I2S0_RX_MCLK/I2S0_TX_SCK/I2S0_TX_MCLK/SSP0_SCK_A8") (pintype "passive"))
    )
    (net (code "72") (name "unconnected-(U2B-P3_1{slash}I2S0_TX_WS{slash}I2S0_RX_WS{slash}CAN0_RD{slash}USB1_IND1{slash}GPIO5[8]{slash}LCD_VD15-PadF7)") (class "Default")
      (node (ref "U2") (pin "F7") (pinfunction "P3_1/I2S0_TX_WS/I2S0_RX_WS/CAN0_RD/USB1_IND1/GPIO5[8]/LCD_VD15_F7") (pintype "passive"))
    )
    (net (code "73") (name "unconnected-(U2B-P3_2{slash}I2S0_TX_SDA{slash}I2S0_RX_SDA{slash}CAN0_TD{slash}USB1_IND0{slash}GPIO5[9]{slash}LCD_VD14-PadG6)") (class "Default")
      (node (ref "U2") (pin "G6") (pinfunction "P3_2/I2S0_TX_SDA/I2S0_RX_SDA/CAN0_TD/USB1_IND0/GPIO5[9]/LCD_VD14_G6") (pintype "passive"))
    )
    (net (code "74") (name "unconnected-(U2B-P3_3{slash}SPI_SCK{slash}SSP0_SCK{slash}SPIFI_SCK{slash}CGU_OUT1{slash}I2S0_TX_MCLK{slash}I2S1_TX_SCK-PadA7)") (class "Default")
      (node (ref "U2") (pin "A7") (pinfunction "P3_3/SPI_SCK/SSP0_SCK/SPIFI_SCK/CGU_OUT1/I2S0_TX_MCLK/I2S1_TX_SCK_A7") (pintype "passive"))
    )
    (net (code "75") (name "unconnected-(U2B-P3_4{slash}GPIO1[14]{slash}SPIFI_SIO3{slash}U1_TXD{slash}I2S0_TX_WS{slash}I2S1_RX_SDA{slash}LCD_VD13-PadB8)") (class "Default")
      (node (ref "U2") (pin "B8") (pinfunction "P3_4/GPIO1[14]/SPIFI_SIO3/U1_TXD/I2S0_TX_WS/I2S1_RX_SDA/LCD_VD13_B8") (pintype "passive"))
    )
    (net (code "76") (name "unconnected-(U2B-P3_5{slash}GPIO1[15]{slash}SPIFI_SIO2{slash}U1_RXD{slash}I2S0_TX_SDA{slash}I2S1_RX_WS{slash}LCD_VD12-PadB7)") (class "Default")
      (node (ref "U2") (pin "B7") (pinfunction "P3_5/GPIO1[15]/SPIFI_SIO2/U1_RXD/I2S0_TX_SDA/I2S1_RX_WS/LCD_VD12_B7") (pintype "passive"))
    )
    (net (code "77") (name "unconnected-(U2B-P3_6{slash}GPIO0[6]{slash}SPI_MISO{slash}SSP0_SSEL{slash}SPIFI_MISO{slash}SSP0_MISO-PadC7)") (class "Default")
      (node (ref "U2") (pin "C7") (pinfunction "P3_6/GPIO0[6]/SPI_MISO/SSP0_SSEL/SPIFI_MISO/SSP0_MISO_C7") (pintype "passive"))
    )
    (net (code "78") (name "unconnected-(U2B-P3_7{slash}SPI_MOSI{slash}SSP0_MISO{slash}SPIFI_MOSI{slash}GPIO5[10]{slash}SSP0_MOSI-PadD7)") (class "Default")
      (node (ref "U2") (pin "D7") (pinfunction "P3_7/SPI_MOSI/SSP0_MISO/SPIFI_MOSI/GPIO5[10]/SSP0_MOSI_D7") (pintype "passive"))
    )
    (net (code "79") (name "unconnected-(U2B-P3_8{slash}SPI_SSEL{slash}SSP0_MOSI{slash}SPIFI_CS{slash}GPIO5[11]{slash}SSP0_SSEL-PadE7)") (class "Default")
      (node (ref "U2") (pin "E7") (pinfunction "P3_8/SPI_SSEL/SSP0_MOSI/SPIFI_CS/GPIO5[11]/SSP0_SSEL_E7") (pintype "passive"))
    )
    (net (code "80") (name "unconnected-(U2C-P6_0{slash}I2S0_RX_MCLK{slash}I2S0_RX_SCK-PadH7)") (class "Default")
      (node (ref "U2") (pin "H7") (pinfunction "P6_0/I2S0_RX_MCLK/I2S0_RX_SCK_H7") (pintype "passive"))
    )
    (net (code "81") (name "unconnected-(U2C-P6_1{slash}GPIO3[0]{slash}EMC_DYCS1{slash}U0_UCLK{slash}I2S0_RX_WS{slash}T2_CAP0-PadG5)") (class "Default")
      (node (ref "U2") (pin "G5") (pinfunction "P6_1/GPIO3[0]/EMC_DYCS1/U0_UCLK/I2S0_RX_WS/T2_CAP0_G5") (pintype "passive"))
    )
    (net (code "82") (name "unconnected-(U2C-P6_4{slash}GPIO3[3]{slash}CTIN_6{slash}U0_TXD{slash}~{EMC_CAS}-PadF6)") (class "Default")
      (node (ref "U2") (pin "F6") (pinfunction "P6_4/GPIO3[3]/CTIN_6/U0_TXD/~{EMC_CAS}_F6") (pintype "passive"))
    )
    (net (code "83") (name "unconnected-(U2C-PF_4{slash}SSP1_SCK{slash}GP_CLKIN{slash}TRACECLK{slash}I2S0_TX_MCLK{slash}I2S0_RX_SCK-PadH4)") (class "Default")
      (node (ref "U2") (pin "H4") (pinfunction "PF_4/SSP1_SCK/GP_CLKIN/TRACECLK/I2S0_TX_MCLK/I2S0_RX_SCK_H4") (pintype "passive"))
    )
    (net (code "84") (name "unconnected-(U11-NC-Pad1)") (class "Default")
      (node (ref "U11") (pin "1") (pinfunction "NC_1") (pintype "passive"))
    )
    (net (code "85") (name "unconnected-(U14-1Z-Pad16)") (class "Default")
      (node (ref "U14") (pin "16") (pinfunction "1Z_16") (pintype "passive"))
    )
    (net (code "86") (name "unconnected-(U14-4Y0-Pad13)") (class "Default")
      (node (ref "U14") (pin "13") (pinfunction "4Y0_13") (pintype "passive"))
    )
    (net (code "87") (name "unconnected-(U14-NC-Pad10)") (class "Default")
      (node (ref "U14") (pin "10") (pinfunction "NC_10") (pintype "passive"))
    )
  )
)
